# TPS.net
KiCad netlist of a schematic drawn in EAGLE
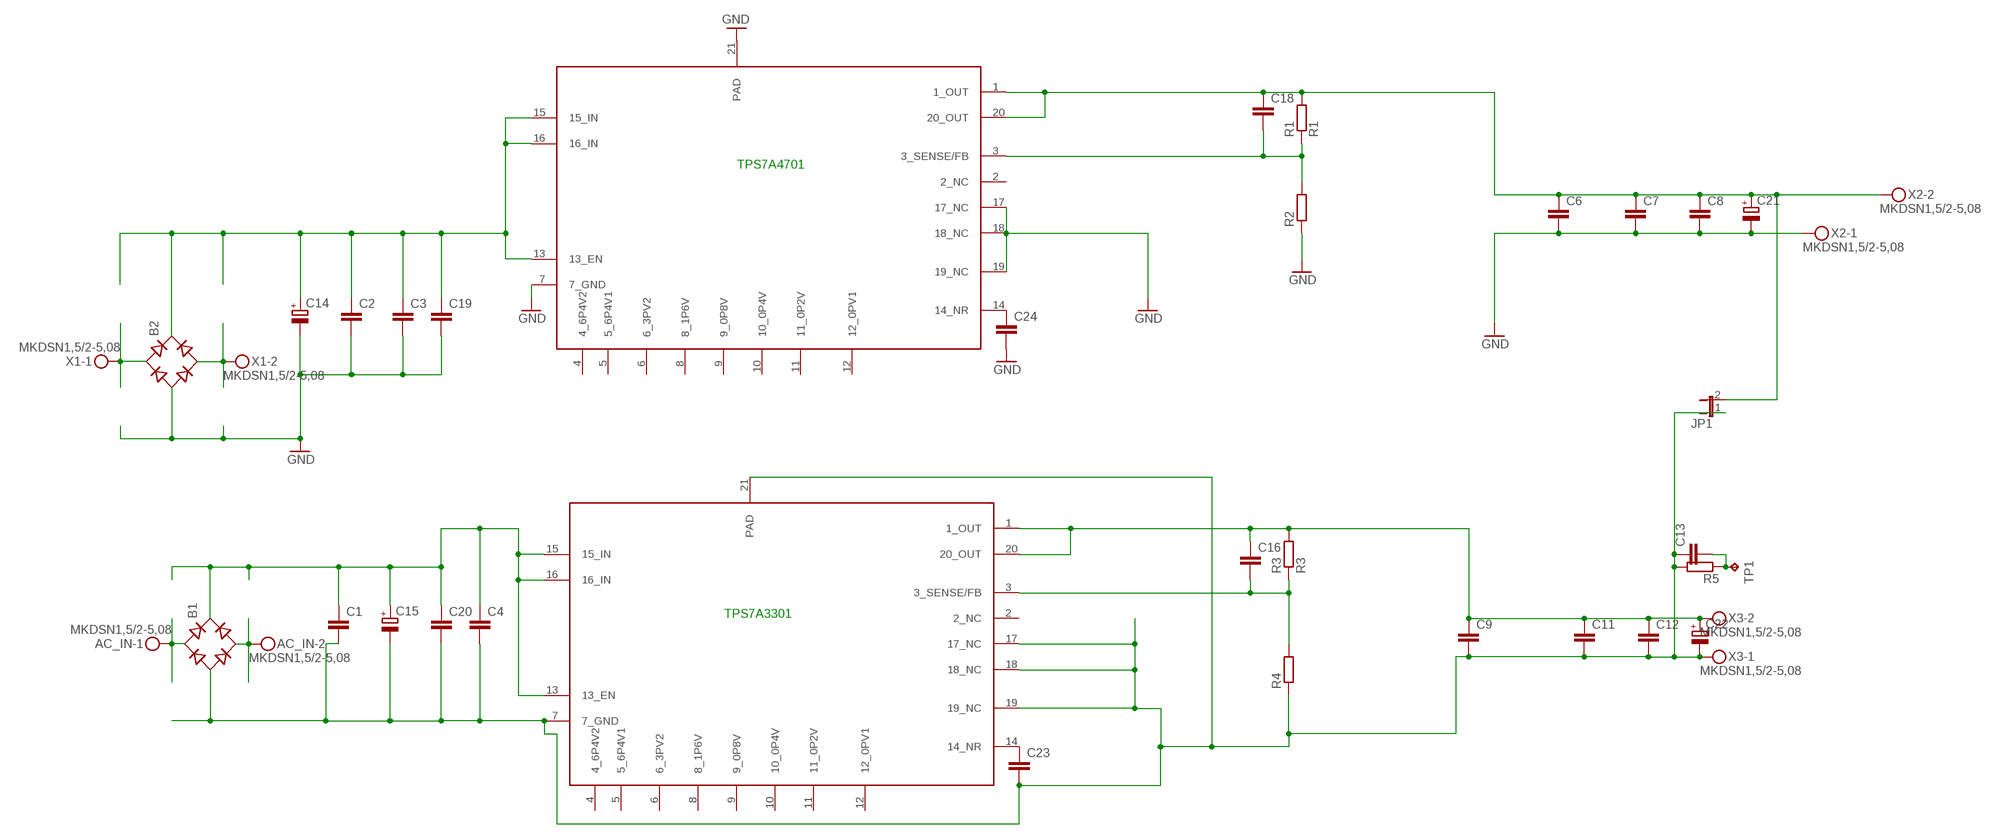
[diagram p0: schematic, sheet 1]

(export (version "E")
  (design (tool "Eeschema 10.0.6"))
  (components
    (comp (ref "AC_IN")
      (value "MKDSN1,5/2-5,08")
      (footprint "eagle-import:MKDSN1,5_2-5,08")
      (libsource (lib "eagle-import") (part "MKDSN1,5/2-5,08"))
    )
    (comp (ref "B1")
      (value "RB1A")
      (footprint "eagle-import:RB1A")
      (libsource (lib "eagle-import") (part "RB1A"))
    )
    (comp (ref "B2")
      (value "RB1A")
      (footprint "eagle-import:RB1A")
      (libsource (lib "eagle-import") (part "RB1A"))
    )
    (comp (ref "C1")
      (value "C-EUC1210")
      (footprint "eagle-import:C1210")
      (libsource (lib "eagle-import") (part "C-EUC1210"))
    )
    (comp (ref "C2")
      (value "C-EUC1210")
      (footprint "eagle-import:C1210")
      (libsource (lib "eagle-import") (part "C-EUC1210"))
    )
    (comp (ref "C3")
      (value "C-EUC0805")
      (footprint "eagle-import:C0805")
      (libsource (lib "eagle-import") (part "C-EUC0805"))
    )
    (comp (ref "C4")
      (value "C-EUC0805")
      (footprint "eagle-import:C0805")
      (libsource (lib "eagle-import") (part "C-EUC0805"))
    )
    (comp (ref "C6")
      (value "C-EUC0603")
      (footprint "eagle-import:C0603")
      (libsource (lib "eagle-import") (part "C-EUC0603"))
    )
    (comp (ref "C7")
      (value "C-EUC0805")
      (footprint "eagle-import:C0805")
      (libsource (lib "eagle-import") (part "C-EUC0805"))
    )
    (comp (ref "C8")
      (value "C-EUC1210")
      (footprint "eagle-import:C1210")
      (libsource (lib "eagle-import") (part "C-EUC1210"))
    )
    (comp (ref "C9")
      (value "C-EUC0603")
      (footprint "eagle-import:C0603")
      (libsource (lib "eagle-import") (part "C-EUC0603"))
    )
    (comp (ref "C11")
      (value "C-EUC1210")
      (footprint "eagle-import:C1210")
      (libsource (lib "eagle-import") (part "C-EUC1210"))
    )
    (comp (ref "C12")
      (value "C-EUC0805")
      (footprint "eagle-import:C0805")
      (libsource (lib "eagle-import") (part "C-EUC0805"))
    )
    (comp (ref "C13")
      (value "C-EU075-042X103")
      (footprint "eagle-import:C075-042X103")
      (libsource (lib "eagle-import") (part "C-EU075-042X103"))
    )
    (comp (ref "C14")
      (value "CPOL-EUE5-13")
      (footprint "eagle-import:E5-13")
      (libsource (lib "eagle-import") (part "CPOL-EUE5-13"))
    )
    (comp (ref "C15")
      (value "CPOL-EUE5-13")
      (footprint "eagle-import:E5-13")
      (libsource (lib "eagle-import") (part "CPOL-EUE5-13"))
    )
    (comp (ref "C16")
      (value "C-EUC0603")
      (footprint "eagle-import:C0603")
      (libsource (lib "eagle-import") (part "C-EUC0603"))
    )
    (comp (ref "C18")
      (value "C-EUC0603")
      (footprint "eagle-import:C0603")
      (libsource (lib "eagle-import") (part "C-EUC0603"))
    )
    (comp (ref "C19")
      (value "C-EUC0603")
      (footprint "eagle-import:C0603")
      (libsource (lib "eagle-import") (part "C-EUC0603"))
    )
    (comp (ref "C20")
      (value "C-EUC0603")
      (footprint "eagle-import:C0603")
      (libsource (lib "eagle-import") (part "C-EUC0603"))
    )
    (comp (ref "C21")
      (value "CPOL-EUE3.5-8")
      (footprint "eagle-import:E3,5-8")
      (libsource (lib "eagle-import") (part "CPOL-EUE3.5-8"))
    )
    (comp (ref "C22")
      (value "CPOL-EUE3.5-8")
      (footprint "eagle-import:E3,5-8")
      (libsource (lib "eagle-import") (part "CPOL-EUE3.5-8"))
    )
    (comp (ref "C23")
      (value "C-EUC0603")
      (footprint "eagle-import:C0603")
      (libsource (lib "eagle-import") (part "C-EUC0603"))
    )
    (comp (ref "C24")
      (value "C-EUC0603")
      (footprint "eagle-import:C0603")
      (libsource (lib "eagle-import") (part "C-EUC0603"))
    )
    (comp (ref "JP1")
      (value "JP1E")
      (footprint "eagle-import:JP1")
      (libsource (lib "eagle-import") (part "JP1E"))
    )
    (comp (ref "R1")
      (value "R1")
      (footprint "eagle-import:R0805")
      (libsource (lib "eagle-import") (part "R-EU_R0805"))
    )
    (comp (ref "R2")
      (value "R-EU_R0805")
      (footprint "eagle-import:R0805")
      (libsource (lib "eagle-import") (part "R-EU_R0805"))
    )
    (comp (ref "R3")
      (value "R3")
      (footprint "eagle-import:R0805")
      (libsource (lib "eagle-import") (part "R-EU_R0805"))
    )
    (comp (ref "R4")
      (value "R-EU_R0805")
      (footprint "eagle-import:R0805")
      (libsource (lib "eagle-import") (part "R-EU_R0805"))
    )
    (comp (ref "R5")
      (value "R-EU_0207/12")
      (footprint "eagle-import:0207_12")
      (libsource (lib "eagle-import") (part "R-EU_0207/12"))
    )
    (comp (ref "TP1")
      (value "TPPAD1-13")
      (footprint "eagle-import:P1-13")
      (libsource (lib "eagle-import") (part "TPPAD1-13"))
    )
    (comp (ref "U$1")
      (value "TPS7A4701")
      (footprint "eagle-import:QFN65P500X500X100-21N")
      (libsource (lib "eagle-import") (part "TPS7A4701"))
    )
    (comp (ref "U$2")
      (value "TPS7A4701")
      (footprint "eagle-import:QFN65P500X500X100-21N")
      (libsource (lib "eagle-import") (part "TPS7A4701"))
    )
    (comp (ref "X1")
      (value "MKDSN1,5/2-5,08")
      (footprint "eagle-import:MKDSN1,5_2-5,08")
      (libsource (lib "eagle-import") (part "MKDSN1,5/2-5,08"))
    )
    (comp (ref "X2")
      (value "MKDSN1,5/2-5,08")
      (footprint "eagle-import:MKDSN1,5_2-5,08")
      (libsource (lib "eagle-import") (part "MKDSN1,5/2-5,08"))
    )
    (comp (ref "X3")
      (value "MKDSN1,5/2-5,08")
      (footprint "eagle-import:MKDSN1,5_2-5,08")
      (libsource (lib "eagle-import") (part "MKDSN1,5/2-5,08"))
    )
  )
  (nets
    (net (code "1") (name "GND") (class "Default")
      (node (ref "B2") (pin "-") (pinfunction "-_-") (pintype "passive"))
      (node (ref "C14") (pin "-") (pinfunction "-_-") (pintype "passive"))
      (node (ref "C19") (pin "2") (pinfunction "2_2") (pintype "passive"))
      (node (ref "C2") (pin "2") (pinfunction "2_2") (pintype "passive"))
      (node (ref "C21") (pin "-") (pinfunction "-_-") (pintype "passive"))
      (node (ref "C24") (pin "2") (pinfunction "2_2") (pintype "passive"))
      (node (ref "C3") (pin "2") (pinfunction "2_2") (pintype "passive"))
      (node (ref "C6") (pin "2") (pinfunction "2_2") (pintype "passive"))
      (node (ref "C7") (pin "2") (pinfunction "2_2") (pintype "passive"))
      (node (ref "C8") (pin "2") (pinfunction "2_2") (pintype "passive"))
      (node (ref "R2") (pin "1") (pinfunction "1_1") (pintype "passive"))
      (node (ref "U$1") (pin "17") (pinfunction "17_NC_17") (pintype "bidirectional"))
      (node (ref "U$1") (pin "18") (pinfunction "18_NC_18") (pintype "bidirectional"))
      (node (ref "U$1") (pin "19") (pinfunction "19_NC_19") (pintype "bidirectional"))
      (node (ref "U$1") (pin "21") (pinfunction "PAD_21") (pintype "bidirectional"))
      (node (ref "U$1") (pin "7") (pinfunction "7_GND_7") (pintype "bidirectional"))
      (node (ref "X2") (pin "1") (pinfunction "KL_1") (pintype "passive"))
    )
    (net (code "2") (name "Net-(AC_INA-KL)") (class "Default")
      (node (ref "AC_IN") (pin "1") (pinfunction "KL_1") (pintype "passive"))
      (node (ref "B1") (pin "AC1") (pinfunction "AC1_AC1") (pintype "passive"))
    )
    (net (code "3") (name "Net-(AC_INB-KL)") (class "Default")
      (node (ref "AC_IN") (pin "2") (pinfunction "KL_2") (pintype "passive"))
      (node (ref "B1") (pin "AC2") (pinfunction "AC2_AC2") (pintype "passive"))
    )
    (net (code "4") (name "Net-(C13-Pad2)") (class "Default")
      (node (ref "C13") (pin "2") (pinfunction "2_2") (pintype "passive"))
      (node (ref "R5") (pin "1") (pinfunction "1_1") (pintype "passive"))
      (node (ref "TP1") (pin "TP") (pinfunction "TP_TP") (pintype "input"))
    )
    (net (code "5") (name "Net-(U$1-1_OUT)") (class "Default")
      (node (ref "C18") (pin "1") (pinfunction "1_1") (pintype "passive"))
      (node (ref "C21") (pin "+") (pinfunction "+_+") (pintype "passive"))
      (node (ref "C6") (pin "1") (pinfunction "1_1") (pintype "passive"))
      (node (ref "C7") (pin "1") (pinfunction "1_1") (pintype "passive"))
      (node (ref "C8") (pin "1") (pinfunction "1_1") (pintype "passive"))
      (node (ref "JP1") (pin "2") (pinfunction "2_2") (pintype "passive"))
      (node (ref "R1") (pin "2") (pinfunction "2_2") (pintype "passive"))
      (node (ref "U$1") (pin "1") (pinfunction "1_OUT_1") (pintype "bidirectional"))
      (node (ref "U$1") (pin "20") (pinfunction "20_OUT_20") (pintype "bidirectional"))
      (node (ref "X2") (pin "2") (pinfunction "KL_2") (pintype "passive"))
    )
    (net (code "6") (name "Net-(U$1-3_SENSE{slash}FB)") (class "Default")
      (node (ref "C18") (pin "2") (pinfunction "2_2") (pintype "passive"))
      (node (ref "R1") (pin "1") (pinfunction "1_1") (pintype "passive"))
      (node (ref "R2") (pin "2") (pinfunction "2_2") (pintype "passive"))
      (node (ref "U$1") (pin "3") (pinfunction "3_SENSE/FB_3") (pintype "bidirectional"))
    )
    (net (code "7") (name "Net-(U$1-13_EN)") (class "Default")
      (node (ref "B2") (pin "+") (pinfunction "+_+") (pintype "passive"))
      (node (ref "C14") (pin "+") (pinfunction "+_+") (pintype "passive"))
      (node (ref "C19") (pin "1") (pinfunction "1_1") (pintype "passive"))
      (node (ref "C2") (pin "1") (pinfunction "1_1") (pintype "passive"))
      (node (ref "C3") (pin "1") (pinfunction "1_1") (pintype "passive"))
      (node (ref "U$1") (pin "13") (pinfunction "13_EN_13") (pintype "bidirectional"))
      (node (ref "U$1") (pin "15") (pinfunction "15_IN_15") (pintype "bidirectional"))
      (node (ref "U$1") (pin "16") (pinfunction "16_IN_16") (pintype "bidirectional"))
    )
    (net (code "8") (name "Net-(U$1-14_NR)") (class "Default")
      (node (ref "C24") (pin "1") (pinfunction "1_1") (pintype "passive"))
      (node (ref "U$1") (pin "14") (pinfunction "14_NR_14") (pintype "bidirectional"))
    )
    (net (code "9") (name "Net-(U$2-1_OUT)") (class "Default")
      (node (ref "C11") (pin "1") (pinfunction "1_1") (pintype "passive"))
      (node (ref "C12") (pin "1") (pinfunction "1_1") (pintype "passive"))
      (node (ref "C16") (pin "1") (pinfunction "1_1") (pintype "passive"))
      (node (ref "C22") (pin "+") (pinfunction "+_+") (pintype "passive"))
      (node (ref "C9") (pin "1") (pinfunction "1_1") (pintype "passive"))
      (node (ref "R3") (pin "2") (pinfunction "2_2") (pintype "passive"))
      (node (ref "U$2") (pin "1") (pinfunction "1_OUT_1") (pintype "bidirectional"))
      (node (ref "U$2") (pin "20") (pinfunction "20_OUT_20") (pintype "bidirectional"))
      (node (ref "X3") (pin "2") (pinfunction "KL_2") (pintype "passive"))
    )
    (net (code "10") (name "Net-(U$2-3_SENSE{slash}FB)") (class "Default")
      (node (ref "C16") (pin "2") (pinfunction "2_2") (pintype "passive"))
      (node (ref "R3") (pin "1") (pinfunction "1_1") (pintype "passive"))
      (node (ref "R4") (pin "2") (pinfunction "2_2") (pintype "passive"))
      (node (ref "U$2") (pin "3") (pinfunction "3_SENSE/FB_3") (pintype "bidirectional"))
    )
    (net (code "11") (name "Net-(U$2-13_EN)") (class "Default")
      (node (ref "B1") (pin "+") (pinfunction "+_+") (pintype "passive"))
      (node (ref "C1") (pin "1") (pinfunction "1_1") (pintype "passive"))
      (node (ref "C15") (pin "+") (pinfunction "+_+") (pintype "passive"))
      (node (ref "C20") (pin "1") (pinfunction "1_1") (pintype "passive"))
      (node (ref "C4") (pin "1") (pinfunction "1_1") (pintype "passive"))
      (node (ref "U$2") (pin "13") (pinfunction "13_EN_13") (pintype "bidirectional"))
      (node (ref "U$2") (pin "15") (pinfunction "15_IN_15") (pintype "bidirectional"))
      (node (ref "U$2") (pin "16") (pinfunction "16_IN_16") (pintype "bidirectional"))
    )
    (net (code "12") (name "Net-(U$2-14_NR)") (class "Default")
      (node (ref "C23") (pin "1") (pinfunction "1_1") (pintype "passive"))
      (node (ref "U$2") (pin "14") (pinfunction "14_NR_14") (pintype "bidirectional"))
    )
    (net (code "13") (name "Net-(U$2-17_NC)") (class "Default")
      (node (ref "B1") (pin "-") (pinfunction "-_-") (pintype "passive"))
      (node (ref "C1") (pin "2") (pinfunction "2_2") (pintype "passive"))
      (node (ref "C11") (pin "2") (pinfunction "2_2") (pintype "passive"))
      (node (ref "C12") (pin "2") (pinfunction "2_2") (pintype "passive"))
      (node (ref "C13") (pin "1") (pinfunction "1_1") (pintype "passive"))
      (node (ref "C15") (pin "-") (pinfunction "-_-") (pintype "passive"))
      (node (ref "C20") (pin "2") (pinfunction "2_2") (pintype "passive"))
      (node (ref "C22") (pin "-") (pinfunction "-_-") (pintype "passive"))
      (node (ref "C23") (pin "2") (pinfunction "2_2") (pintype "passive"))
      (node (ref "C4") (pin "2") (pinfunction "2_2") (pintype "passive"))
      (node (ref "C9") (pin "2") (pinfunction "2_2") (pintype "passive"))
      (node (ref "JP1") (pin "1") (pinfunction "1_1") (pintype "passive"))
      (node (ref "R4") (pin "1") (pinfunction "1_1") (pintype "passive"))
      (node (ref "R5") (pin "2") (pinfunction "2_2") (pintype "passive"))
      (node (ref "U$2") (pin "17") (pinfunction "17_NC_17") (pintype "bidirectional"))
      (node (ref "U$2") (pin "18") (pinfunction "18_NC_18") (pintype "bidirectional"))
      (node (ref "U$2") (pin "19") (pinfunction "19_NC_19") (pintype "bidirectional"))
      (node (ref "U$2") (pin "21") (pinfunction "PAD_21") (pintype "bidirectional"))
      (node (ref "U$2") (pin "7") (pinfunction "7_GND_7") (pintype "bidirectional"))
      (node (ref "X3") (pin "1") (pinfunction "KL_1") (pintype "passive"))
    )
    (net (code "14") (name "Net-(X1A-KL)") (class "Default")
      (node (ref "B2") (pin "AC1") (pinfunction "AC1_AC1") (pintype "passive"))
      (node (ref "X1") (pin "1") (pinfunction "KL_1") (pintype "passive"))
    )
    (net (code "15") (name "Net-(X1B-KL)") (class "Default")
      (node (ref "B2") (pin "AC2") (pinfunction "AC2_AC2") (pintype "passive"))
      (node (ref "X1") (pin "2") (pinfunction "KL_2") (pintype "passive"))
    )
    (net (code "16") (name "unconnected-(U$1-2_NC-Pad2)") (class "Default")
      (node (ref "U$1") (pin "2") (pinfunction "2_NC_2") (pintype "bidirectional"))
    )
    (net (code "17") (name "unconnected-(U$1-4_6P4V2-Pad4)") (class "Default")
      (node (ref "U$1") (pin "4") (pinfunction "4_6P4V2_4") (pintype "bidirectional"))
    )
    (net (code "18") (name "unconnected-(U$1-5_6P4V1-Pad5)") (class "Default")
      (node (ref "U$1") (pin "5") (pinfunction "5_6P4V1_5") (pintype "bidirectional"))
    )
    (net (code "19") (name "unconnected-(U$1-6_3PV2-Pad6)") (class "Default")
      (node (ref "U$1") (pin "6") (pinfunction "6_3PV2_6") (pintype "bidirectional"))
    )
    (net (code "20") (name "unconnected-(U$1-8_1P6V-Pad8)") (class "Default")
      (node (ref "U$1") (pin "8") (pinfunction "8_1P6V_8") (pintype "bidirectional"))
    )
    (net (code "21") (name "unconnected-(U$1-9_0P8V-Pad9)") (class "Default")
      (node (ref "U$1") (pin "9") (pinfunction "9_0P8V_9") (pintype "bidirectional"))
    )
    (net (code "22") (name "unconnected-(U$1-10_0P4V-Pad10)") (class "Default")
      (node (ref "U$1") (pin "10") (pinfunction "10_0P4V_10") (pintype "bidirectional"))
    )
    (net (code "23") (name "unconnected-(U$1-11_0P2V-Pad11)") (class "Default")
      (node (ref "U$1") (pin "11") (pinfunction "11_0P2V_11") (pintype "bidirectional"))
    )
    (net (code "24") (name "unconnected-(U$1-12_0PV1-Pad12)") (class "Default")
      (node (ref "U$1") (pin "12") (pinfunction "12_0PV1_12") (pintype "bidirectional"))
    )
    (net (code "25") (name "unconnected-(U$2-2_NC-Pad2)") (class "Default")
      (node (ref "U$2") (pin "2") (pinfunction "2_NC_2") (pintype "bidirectional"))
    )
    (net (code "26") (name "unconnected-(U$2-4_6P4V2-Pad4)") (class "Default")
      (node (ref "U$2") (pin "4") (pinfunction "4_6P4V2_4") (pintype "bidirectional"))
    )
    (net (code "27") (name "unconnected-(U$2-5_6P4V1-Pad5)") (class "Default")
      (node (ref "U$2") (pin "5") (pinfunction "5_6P4V1_5") (pintype "bidirectional"))
    )
    (net (code "28") (name "unconnected-(U$2-6_3PV2-Pad6)") (class "Default")
      (node (ref "U$2") (pin "6") (pinfunction "6_3PV2_6") (pintype "bidirectional"))
    )
    (net (code "29") (name "unconnected-(U$2-8_1P6V-Pad8)") (class "Default")
      (node (ref "U$2") (pin "8") (pinfunction "8_1P6V_8") (pintype "bidirectional"))
    )
    (net (code "30") (name "unconnected-(U$2-9_0P8V-Pad9)") (class "Default")
      (node (ref "U$2") (pin "9") (pinfunction "9_0P8V_9") (pintype "bidirectional"))
    )
    (net (code "31") (name "unconnected-(U$2-10_0P4V-Pad10)") (class "Default")
      (node (ref "U$2") (pin "10") (pinfunction "10_0P4V_10") (pintype "bidirectional"))
    )
    (net (code "32") (name "unconnected-(U$2-11_0P2V-Pad11)") (class "Default")
      (node (ref "U$2") (pin "11") (pinfunction "11_0P2V_11") (pintype "bidirectional"))
    )
    (net (code "33") (name "unconnected-(U$2-12_0PV1-Pad12)") (class "Default")
      (node (ref "U$2") (pin "12") (pinfunction "12_0PV1_12") (pintype "bidirectional"))
    )
  )
)
